# Arduino_Mini.net
KiCad netlist of a schematic drawn in EAGLE
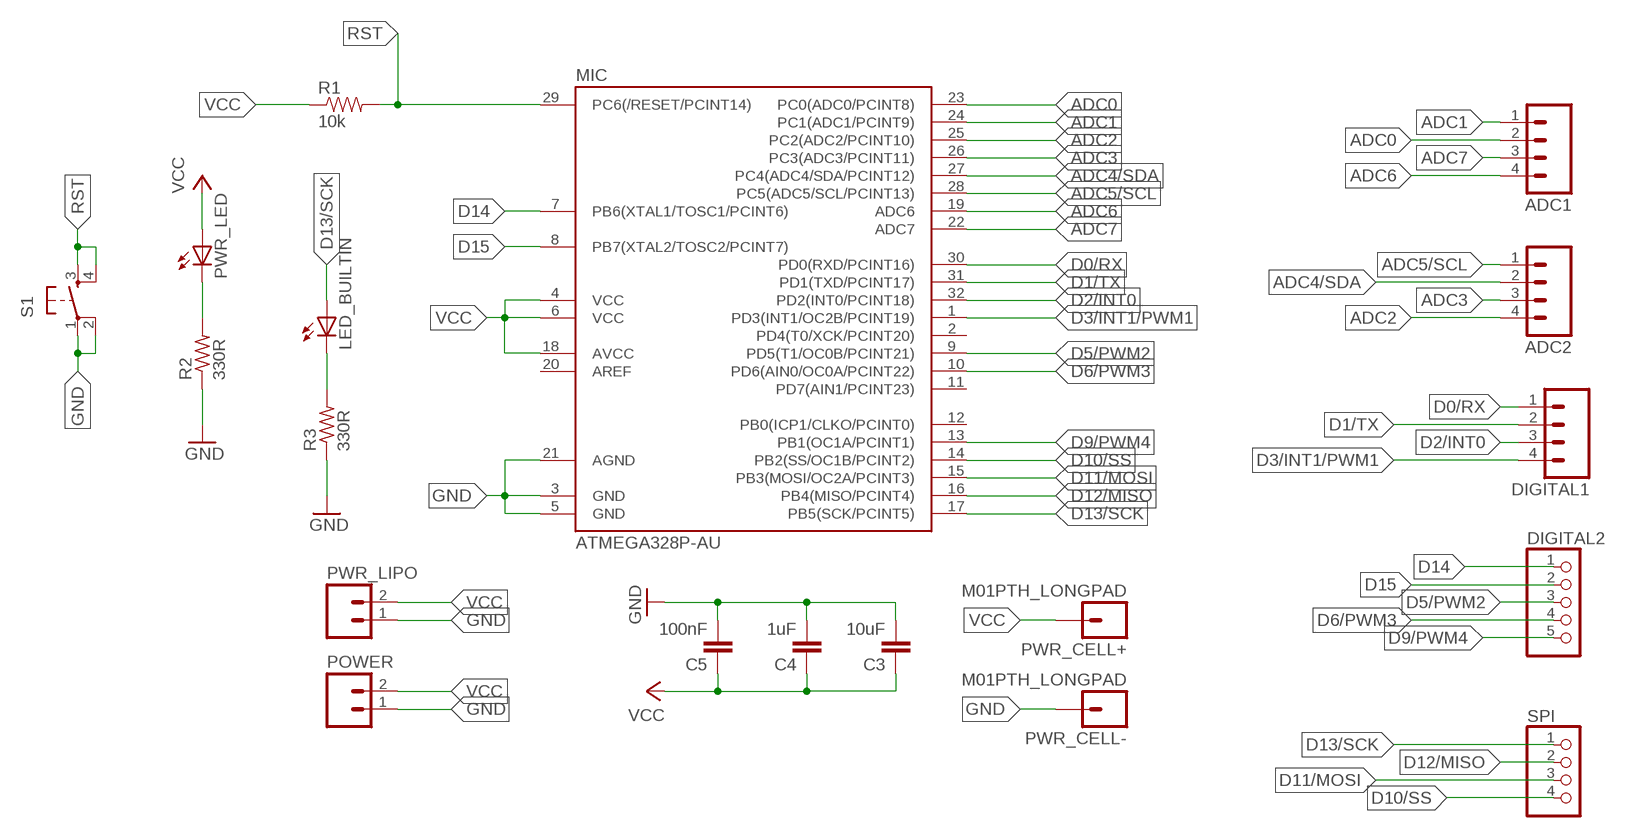
[diagram p0: schematic, sheet 1]

(export (version "E")
  (design (tool "Eeschema 10.0.6"))
  (components
    (comp (ref "ADC1")
      (value "M04LONGPADS")
      (footprint "eagle-import:1X04_LONGPADS")
      (libsource (lib "eagle-import") (part "M04LONGPADS"))
    )
    (comp (ref "ADC2")
      (value "M04LONGPADS")
      (footprint "eagle-import:1X04_LONGPADS")
      (libsource (lib "eagle-import") (part "M04LONGPADS"))
    )
    (comp (ref "C3")
      (value "10uF")
      (footprint "eagle-import:1206")
      (libsource (lib "eagle-import") (part "CAP1206"))
    )
    (comp (ref "C4")
      (value "1uF")
      (footprint "eagle-import:1206")
      (libsource (lib "eagle-import") (part "CAP1206"))
    )
    (comp (ref "C5")
      (value "100nF")
      (footprint "eagle-import:1206")
      (libsource (lib "eagle-import") (part "CAP1206"))
    )
    (comp (ref "DIGITAL1")
      (value "M04LONGPADS")
      (footprint "eagle-import:1X04_LONGPADS")
      (libsource (lib "eagle-import") (part "M04LONGPADS"))
    )
    (comp (ref "DIGITAL2")
      (value "PINHD-1X5")
      (footprint "eagle-import:1X05")
      (libsource (lib "eagle-import") (part "PINHD-1X5"))
    )
    (comp (ref "LED_BUILTIN")
      (value "LED1206")
      (footprint "eagle-import:1206")
      (libsource (lib "eagle-import") (part "LED1206"))
    )
    (comp (ref "MIC")
      (value "ATMEGA328P-AU")
      (footprint "eagle-import:TQFP32-08")
      (libsource (lib "eagle-import") (part "ATMEGA48/88/168-AU"))
    )
    (comp (ref "POWER")
      (value "M02LOCK_LONGPADS")
      (footprint "eagle-import:1X02_LOCK_LONGPADS")
      (libsource (lib "eagle-import") (part "M02LOCK_LONGPADS"))
    )
    (comp (ref "PWR_CELL+")
      (value "M01PTH_LONGPAD")
      (footprint "eagle-import:1X01_LONGPAD")
      (libsource (lib "eagle-import") (part "M01PTH_LONGPAD"))
    )
    (comp (ref "PWR_CELL-")
      (value "M01PTH_LONGPAD")
      (footprint "eagle-import:1X01_LONGPAD")
      (libsource (lib "eagle-import") (part "M01PTH_LONGPAD"))
    )
    (comp (ref "PWR_LED")
      (value "LED1206")
      (footprint "eagle-import:1206")
      (libsource (lib "eagle-import") (part "LED1206"))
    )
    (comp (ref "PWR_LIPO")
      (value "M02LOCK_LONGPADS")
      (footprint "eagle-import:1X02_LOCK_LONGPADS")
      (libsource (lib "eagle-import") (part "M02LOCK_LONGPADS"))
    )
    (comp (ref "R1")
      (value "10k")
      (footprint "eagle-import:1206")
      (libsource (lib "eagle-import") (part "RESISTOR1206"))
    )
    (comp (ref "R2")
      (value "330R")
      (footprint "eagle-import:1206")
      (libsource (lib "eagle-import") (part "FAB_Hello_RESISTOR1206"))
    )
    (comp (ref "R3")
      (value "330R")
      (footprint "eagle-import:1206")
      (libsource (lib "eagle-import") (part "FAB_Hello_RESISTOR1206"))
    )
    (comp (ref "S1")
      (value "6MM_SWITCH6MM_SWITCH")
      (footprint "eagle-import:6MM_SWITCH")
      (libsource (lib "eagle-import") (part "6MM_SWITCH6MM_SWITCH"))
    )
    (comp (ref "SPI")
      (value "PINHD-1X4")
      (footprint "eagle-import:1X04")
      (libsource (lib "eagle-import") (part "PINHD-1X4"))
    )
  )
  (nets
    (net (code "1") (name "ADC0") (class "Default")
      (node (ref "ADC1") (pin "2") (pinfunction "2_2") (pintype "passive"))
      (node (ref "MIC") (pin "23") (pinfunction "PC0(ADC0/PCINT8)_23") (pintype "bidirectional"))
    )
    (net (code "2") (name "ADC1") (class "Default")
      (node (ref "ADC1") (pin "1") (pinfunction "1_1") (pintype "passive"))
      (node (ref "MIC") (pin "24") (pinfunction "PC1(ADC1/PCINT9)_24") (pintype "bidirectional"))
    )
    (net (code "3") (name "ADC2") (class "Default")
      (node (ref "ADC2") (pin "4") (pinfunction "4_4") (pintype "passive"))
      (node (ref "MIC") (pin "25") (pinfunction "PC2(ADC2/PCINT10)_25") (pintype "bidirectional"))
    )
    (net (code "4") (name "ADC3") (class "Default")
      (node (ref "ADC2") (pin "3") (pinfunction "3_3") (pintype "passive"))
      (node (ref "MIC") (pin "26") (pinfunction "PC3(ADC3/PCINT11)_26") (pintype "bidirectional"))
    )
    (net (code "5") (name "ADC4{slash}SDA") (class "Default")
      (node (ref "ADC2") (pin "2") (pinfunction "2_2") (pintype "passive"))
      (node (ref "MIC") (pin "27") (pinfunction "PC4(ADC4/SDA/PCINT12)_27") (pintype "bidirectional"))
    )
    (net (code "6") (name "ADC5{slash}SCL") (class "Default")
      (node (ref "ADC2") (pin "1") (pinfunction "1_1") (pintype "passive"))
      (node (ref "MIC") (pin "28") (pinfunction "PC5(ADC5/SCL/PCINT13)_28") (pintype "bidirectional"))
    )
    (net (code "7") (name "ADC6") (class "Default")
      (node (ref "ADC1") (pin "4") (pinfunction "4_4") (pintype "passive"))
      (node (ref "MIC") (pin "19") (pinfunction "ADC6_19") (pintype "passive"))
    )
    (net (code "8") (name "ADC7") (class "Default")
      (node (ref "ADC1") (pin "3") (pinfunction "3_3") (pintype "passive"))
      (node (ref "MIC") (pin "22") (pinfunction "ADC7_22") (pintype "passive"))
    )
    (net (code "9") (name "D0{slash}RX") (class "Default")
      (node (ref "DIGITAL1") (pin "1") (pinfunction "1_1") (pintype "passive"))
      (node (ref "MIC") (pin "30") (pinfunction "PD0(RXD/PCINT16)_30") (pintype "bidirectional"))
    )
    (net (code "10") (name "D1{slash}TX") (class "Default")
      (node (ref "DIGITAL1") (pin "2") (pinfunction "2_2") (pintype "passive"))
      (node (ref "MIC") (pin "31") (pinfunction "PD1(TXD/PCINT17)_31") (pintype "bidirectional"))
    )
    (net (code "11") (name "D2{slash}INT0") (class "Default")
      (node (ref "DIGITAL1") (pin "3") (pinfunction "3_3") (pintype "passive"))
      (node (ref "MIC") (pin "32") (pinfunction "PD2(INT0/PCINT18)_32") (pintype "bidirectional"))
    )
    (net (code "12") (name "D3{slash}INT1{slash}PWM1") (class "Default")
      (node (ref "DIGITAL1") (pin "4") (pinfunction "4_4") (pintype "passive"))
      (node (ref "MIC") (pin "1") (pinfunction "PD3(INT1/OC2B/PCINT19)_1") (pintype "bidirectional"))
    )
    (net (code "13") (name "D5{slash}PWM2") (class "Default")
      (node (ref "DIGITAL2") (pin "3") (pinfunction "3_3") (pintype "passive"))
      (node (ref "MIC") (pin "9") (pinfunction "PD5(T1/OC0B/PCINT21)_9") (pintype "bidirectional"))
    )
    (net (code "14") (name "D6{slash}PWM3") (class "Default")
      (node (ref "DIGITAL2") (pin "4") (pinfunction "4_4") (pintype "passive"))
      (node (ref "MIC") (pin "10") (pinfunction "PD6(AIN0/OC0A/PCINT22)_10") (pintype "bidirectional"))
    )
    (net (code "15") (name "D9{slash}PWM4") (class "Default")
      (node (ref "DIGITAL2") (pin "5") (pinfunction "5_5") (pintype "passive"))
      (node (ref "MIC") (pin "13") (pinfunction "PB1(OC1A/PCINT1)_13") (pintype "bidirectional"))
    )
    (net (code "16") (name "D10{slash}SS") (class "Default")
      (node (ref "MIC") (pin "14") (pinfunction "PB2(SS/OC1B/PCINT2)_14") (pintype "bidirectional"))
      (node (ref "SPI") (pin "4") (pinfunction "4_4") (pintype "passive"))
    )
    (net (code "17") (name "D11{slash}MOSI") (class "Default")
      (node (ref "MIC") (pin "15") (pinfunction "PB3(MOSI/OC2A/PCINT3)_15") (pintype "bidirectional"))
      (node (ref "SPI") (pin "3") (pinfunction "3_3") (pintype "passive"))
    )
    (net (code "18") (name "D12{slash}MISO") (class "Default")
      (node (ref "MIC") (pin "16") (pinfunction "PB4(MISO/PCINT4)_16") (pintype "bidirectional"))
      (node (ref "SPI") (pin "2") (pinfunction "2_2") (pintype "passive"))
    )
    (net (code "19") (name "D13{slash}SCK") (class "Default")
      (node (ref "LED_BUILTIN") (pin "1") (pinfunction "A_1") (pintype "passive"))
      (node (ref "MIC") (pin "17") (pinfunction "PB5(SCK/PCINT5)_17") (pintype "bidirectional"))
      (node (ref "SPI") (pin "1") (pinfunction "1_1") (pintype "passive"))
    )
    (net (code "20") (name "D14") (class "Default")
      (node (ref "DIGITAL2") (pin "1") (pinfunction "1_1") (pintype "passive"))
      (node (ref "MIC") (pin "7") (pinfunction "PB6(XTAL1/TOSC1/PCINT6)_7") (pintype "bidirectional"))
    )
    (net (code "21") (name "D15") (class "Default")
      (node (ref "DIGITAL2") (pin "2") (pinfunction "2_2") (pintype "passive"))
      (node (ref "MIC") (pin "8") (pinfunction "PB7(XTAL2/TOSC2/PCINT7)_8") (pintype "bidirectional"))
    )
    (net (code "22") (name "GND") (class "Default")
      (node (ref "C3") (pin "2") (pinfunction "2_2") (pintype "passive"))
      (node (ref "C4") (pin "2") (pinfunction "2_2") (pintype "passive"))
      (node (ref "C5") (pin "2") (pinfunction "2_2") (pintype "passive"))
      (node (ref "MIC") (pin "21") (pinfunction "AGND_21") (pintype "power_in"))
      (node (ref "MIC") (pin "3") (pinfunction "GND_3") (pintype "power_in"))
      (node (ref "MIC") (pin "5") (pinfunction "GND_5") (pintype "power_in"))
      (node (ref "POWER") (pin "1") (pinfunction "1_1") (pintype "passive"))
      (node (ref "PWR_CELL-") (pin "1") (pinfunction "1_1") (pintype "passive"))
      (node (ref "PWR_LIPO") (pin "1") (pinfunction "1_1") (pintype "passive"))
      (node (ref "R2") (pin "1") (pinfunction "1_1") (pintype "passive"))
      (node (ref "R3") (pin "1") (pinfunction "1_1") (pintype "passive"))
      (node (ref "S1") (pin "1") (pinfunction "P_1") (pintype "passive"))
      (node (ref "S1") (pin "2") (pinfunction "P1_2") (pintype "passive"))
    )
    (net (code "23") (name "Net-(LED_BUILTIN-C)") (class "Default")
      (node (ref "LED_BUILTIN") (pin "2") (pinfunction "C_2") (pintype "passive"))
      (node (ref "R3") (pin "2") (pinfunction "2_2") (pintype "passive"))
    )
    (net (code "24") (name "Net-(PWR_LED-C)") (class "Default")
      (node (ref "PWR_LED") (pin "2") (pinfunction "C_2") (pintype "passive"))
      (node (ref "R2") (pin "2") (pinfunction "2_2") (pintype "passive"))
    )
    (net (code "25") (name "RST") (class "Default")
      (node (ref "MIC") (pin "29") (pinfunction "PC6(/RESET/PCINT14)_29") (pintype "bidirectional"))
      (node (ref "R1") (pin "2") (pinfunction "2_2") (pintype "passive"))
      (node (ref "S1") (pin "3") (pinfunction "S_3") (pintype "passive"))
      (node (ref "S1") (pin "4") (pinfunction "S1_4") (pintype "passive"))
    )
    (net (code "26") (name "VCC") (class "Default")
      (node (ref "C3") (pin "1") (pinfunction "1_1") (pintype "passive"))
      (node (ref "C4") (pin "1") (pinfunction "1_1") (pintype "passive"))
      (node (ref "C5") (pin "1") (pinfunction "1_1") (pintype "passive"))
      (node (ref "MIC") (pin "18") (pinfunction "AVCC_18") (pintype "passive"))
      (node (ref "MIC") (pin "4") (pinfunction "VCC_4") (pintype "power_in"))
      (node (ref "MIC") (pin "6") (pinfunction "VCC_6") (pintype "power_in"))
      (node (ref "POWER") (pin "2") (pinfunction "2_2") (pintype "passive"))
      (node (ref "PWR_CELL+") (pin "1") (pinfunction "1_1") (pintype "passive"))
      (node (ref "PWR_LED") (pin "1") (pinfunction "A_1") (pintype "passive"))
      (node (ref "PWR_LIPO") (pin "2") (pinfunction "2_2") (pintype "passive"))
      (node (ref "R1") (pin "1") (pinfunction "1_1") (pintype "passive"))
    )
    (net (code "27") (name "unconnected-(MIC-AREF-Pad20)") (class "Default")
      (node (ref "MIC") (pin "20") (pinfunction "AREF_20") (pintype "passive"))
    )
    (net (code "28") (name "unconnected-(MIC-PB0(ICP1{slash}CLKO{slash}PCINT0)-Pad12)") (class "Default")
      (node (ref "MIC") (pin "12") (pinfunction "PB0(ICP1/CLKO/PCINT0)_12") (pintype "bidirectional"))
    )
    (net (code "29") (name "unconnected-(MIC-PD4(T0{slash}XCK{slash}PCINT20)-Pad2)") (class "Default")
      (node (ref "MIC") (pin "2") (pinfunction "PD4(T0/XCK/PCINT20)_2") (pintype "bidirectional"))
    )
    (net (code "30") (name "unconnected-(MIC-PD7(AIN1{slash}PCINT23)-Pad11)") (class "Default")
      (node (ref "MIC") (pin "11") (pinfunction "PD7(AIN1/PCINT23)_11") (pintype "bidirectional"))
    )
  )
)
